# LambdaIn.net
KiCad netlist of a schematic drawn in Altium Designer
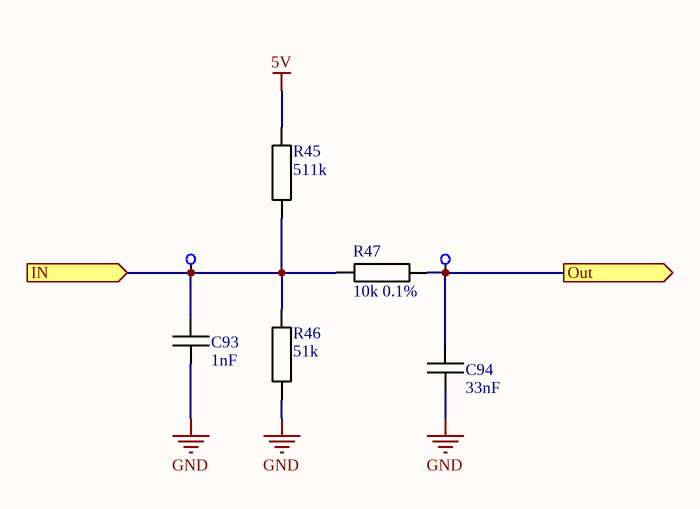
[diagram p0: LambdaIn.SchDoc]

(export (version "E")
  (design (tool "Eeschema 10.0.6"))
  (components
    (comp (ref "C93")
      (value "1nF")
      (footprint "SMD 0603")
      (description "CC0603KRX7R9BB102")
      (libsource (lib "Maks_lib") (part "Capasitor"))
    )
    (comp (ref "C94")
      (value "33nF")
      (footprint "SMD 0603")
      (description "CC0603JRX7R7BB333")
      (libsource (lib "Maks_lib") (part "Capasitor"))
    )
    (comp (ref "R45")
      (value "511k")
      (footprint "SMD 0603")
      (description "RC0603FR-07511KL")
      (libsource (lib "Maks_lib") (part "Resistor"))
    )
    (comp (ref "R46")
      (value "51k")
      (footprint "SMD 0603")
      (description "RC0603FR-0751KL")
      (libsource (lib "Maks_lib") (part "Resistor"))
    )
    (comp (ref "R47")
      (value "10k 0.1%")
      (footprint "SMD 0603")
      (description "RT0603BRD0710KL")
      (libsource (lib "Maks_lib") (part "Resistor"))
    )
    (comp (ref "TP64")
      (value "TestPoint")
      (footprint "TESTPOINT")
      (description "testPoint")
      (libsource (lib "Maks_lib") (part "TestPoint"))
    )
    (comp (ref "TP65")
      (value "TestPoint")
      (footprint "TESTPOINT")
      (description "testPoint")
      (libsource (lib "Maks_lib") (part "TestPoint"))
    )
  )
  (nets
    (net (code "1") (name "/IN") (class "Default")
      (node (ref "C93") (pin "2") (pinfunction "2_2") (pintype "passive"))
      (node (ref "R45") (pin "2") (pinfunction "2_2") (pintype "passive"))
      (node (ref "R46") (pin "1") (pinfunction "1_1") (pintype "passive"))
      (node (ref "R47") (pin "1") (pinfunction "1_1") (pintype "passive"))
      (node (ref "TP64") (pin "0") (pinfunction "0_0") (pintype "passive"))
    )
    (net (code "2") (name "/Out") (class "Default")
      (node (ref "C94") (pin "1") (pinfunction "1_1") (pintype "passive"))
      (node (ref "R47") (pin "2") (pinfunction "2_2") (pintype "passive"))
      (node (ref "TP65") (pin "0") (pinfunction "0_0") (pintype "passive"))
    )
    (net (code "3") (name "5V") (class "Default")
      (node (ref "R45") (pin "1") (pinfunction "1_1") (pintype "passive"))
    )
    (net (code "4") (name "GND") (class "Default")
      (node (ref "C93") (pin "1") (pinfunction "1_1") (pintype "passive"))
      (node (ref "C94") (pin "2") (pinfunction "2_2") (pintype "passive"))
      (node (ref "R46") (pin "2") (pinfunction "2_2") (pintype "passive"))
    )
  )
)
